# Timbre.net
KiCad netlist of a schematic drawn in EAGLE
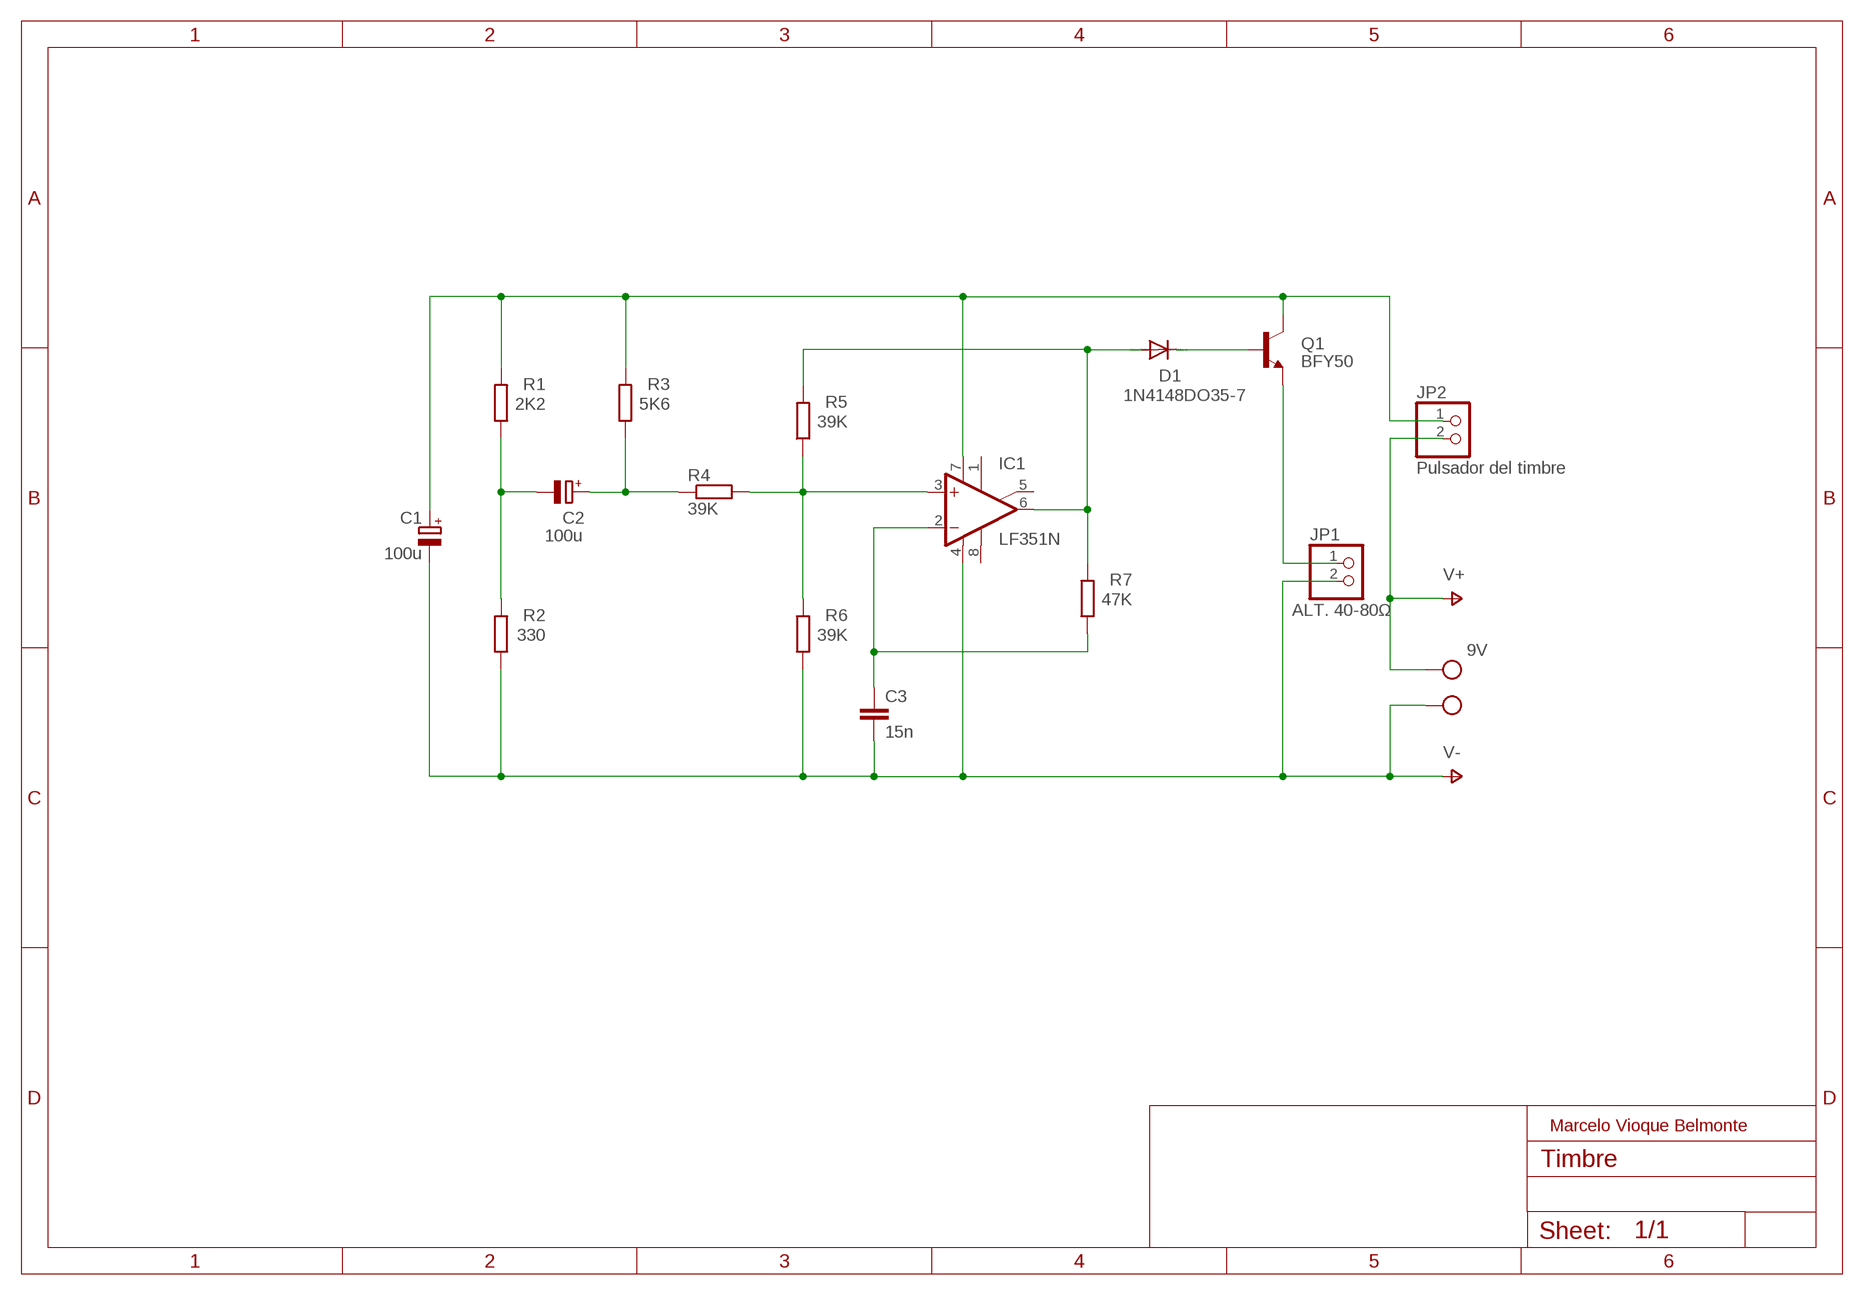
[diagram p0: schematic, sheet 1]

(export (version "E")
  (design (tool "Eeschema 10.0.6"))
  (components
    (comp (ref "C1")
      (value "100u")
      (footprint "eagle-import:E2,5-6")
      (libsource (lib "eagle-import") (part "CPOL-EUE2.5-6"))
    )
    (comp (ref "C2")
      (value "100u")
      (footprint "eagle-import:E2,5-6")
      (libsource (lib "eagle-import") (part "CPOL-EUE2.5-6"))
    )
    (comp (ref "C3")
      (value "15n")
      (footprint "eagle-import:C025_050-025X075")
      (libsource (lib "eagle-import") (part "C-EU025_050-025X075"))
    )
    (comp (ref "D1")
      (value "1N4148DO35-7")
      (footprint "eagle-import:DO35-7")
      (libsource (lib "eagle-import") (part "1N4148DO35-7"))
    )
    (comp (ref "IC1")
      (value "LF351N")
      (footprint "eagle-import:DIL08")
      (libsource (lib "eagle-import") (part "LF351N"))
    )
    (comp (ref "JP1")
      (value "ALT. 40-80Ω")
      (footprint "eagle-import:1X02")
      (libsource (lib "eagle-import") (part "PINHD-1X2"))
    )
    (comp (ref "JP2")
      (value "Pulsador del timbre")
      (footprint "eagle-import:1X02")
      (libsource (lib "eagle-import") (part "PINHD-1X2"))
    )
    (comp (ref "Q1")
      (value "BFY50")
      (footprint "eagle-import:TO39")
      (libsource (lib "eagle-import") (part "BFY50"))
    )
    (comp (ref "R1")
      (value "2K2")
      (footprint "eagle-import:0207_10")
      (libsource (lib "eagle-import") (part "R-EU_0207/10"))
    )
    (comp (ref "R2")
      (value "330")
      (footprint "eagle-import:0207_10")
      (libsource (lib "eagle-import") (part "R-EU_0207/10"))
    )
    (comp (ref "R3")
      (value "5K6")
      (footprint "eagle-import:0207_10")
      (libsource (lib "eagle-import") (part "R-EU_0207/10"))
    )
    (comp (ref "R4")
      (value "39K")
      (footprint "eagle-import:0207_10")
      (libsource (lib "eagle-import") (part "R-EU_0207/10"))
    )
    (comp (ref "R5")
      (value "39K")
      (footprint "eagle-import:0207_10")
      (libsource (lib "eagle-import") (part "R-EU_0207/10"))
    )
    (comp (ref "R6")
      (value "39K")
      (footprint "eagle-import:0207_10")
      (libsource (lib "eagle-import") (part "R-EU_0207/10"))
    )
    (comp (ref "R7")
      (value "47K")
      (footprint "eagle-import:0207_10")
      (libsource (lib "eagle-import") (part "R-EU_0207/10"))
    )
    (comp (ref "X1")
      (value "9V")
      (footprint "eagle-import:AK500_2")
      (libsource (lib "eagle-import") (part "AK500/2"))
    )
  )
  (nets
    (net (code "1") (name "Net-(C2-Pad+)") (class "Default")
      (node (ref "C2") (pin "+") (pinfunction "+_+") (pintype "passive"))
      (node (ref "R3") (pin "1") (pinfunction "1_1") (pintype "passive"))
      (node (ref "R4") (pin "1") (pinfunction "1_1") (pintype "passive"))
    )
    (net (code "2") (name "Net-(C2-Pad-)") (class "Default")
      (node (ref "C2") (pin "-") (pinfunction "-_-") (pintype "passive"))
      (node (ref "R1") (pin "1") (pinfunction "1_1") (pintype "passive"))
      (node (ref "R2") (pin "2") (pinfunction "2_2") (pintype "passive"))
    )
    (net (code "3") (name "Net-(IC1-+IN)") (class "Default")
      (node (ref "IC1") (pin "3") (pinfunction "+IN_3") (pintype "input"))
      (node (ref "R4") (pin "2") (pinfunction "2_2") (pintype "passive"))
      (node (ref "R5") (pin "1") (pinfunction "1_1") (pintype "passive"))
      (node (ref "R6") (pin "2") (pinfunction "2_2") (pintype "passive"))
    )
    (net (code "4") (name "Net-(IC1--IN)") (class "Default")
      (node (ref "C3") (pin "1") (pinfunction "1_1") (pintype "passive"))
      (node (ref "IC1") (pin "2") (pinfunction "-IN_2") (pintype "input"))
      (node (ref "R7") (pin "1") (pinfunction "1_1") (pintype "passive"))
    )
    (net (code "5") (name "Net-(IC1-OUT)") (class "Default")
      (node (ref "D1") (pin "A") (pinfunction "A_A") (pintype "passive"))
      (node (ref "IC1") (pin "6") (pinfunction "OUT_6") (pintype "output"))
      (node (ref "R5") (pin "2") (pinfunction "2_2") (pintype "passive"))
      (node (ref "R7") (pin "2") (pinfunction "2_2") (pintype "passive"))
    )
    (net (code "6") (name "Net-(IC1-V+)") (class "Default")
      (node (ref "C1") (pin "+") (pinfunction "+_+") (pintype "passive"))
      (node (ref "IC1") (pin "7") (pinfunction "V+_7") (pintype "power_in"))
      (node (ref "JP2") (pin "1") (pinfunction "1_1") (pintype "passive"))
      (node (ref "Q1") (pin "3") (pinfunction "C_3") (pintype "passive"))
      (node (ref "R1") (pin "2") (pinfunction "2_2") (pintype "passive"))
      (node (ref "R3") (pin "2") (pinfunction "2_2") (pintype "passive"))
    )
    (net (code "7") (name "Net-(Q1-B)") (class "Default")
      (node (ref "D1") (pin "C") (pinfunction "C_C") (pintype "passive"))
      (node (ref "Q1") (pin "2") (pinfunction "B_2") (pintype "passive"))
    )
    (net (code "8") (name "Net-(Q1-E)") (class "Default")
      (node (ref "JP1") (pin "1") (pinfunction "1_1") (pintype "passive"))
      (node (ref "Q1") (pin "1") (pinfunction "E_1") (pintype "passive"))
    )
    (net (code "9") (name "V+") (class "Default")
      (node (ref "JP2") (pin "2") (pinfunction "2_2") (pintype "passive"))
      (node (ref "X1") (pin "2") (pinfunction "KL_2") (pintype "passive"))
    )
    (net (code "10") (name "V-") (class "Default")
      (node (ref "C1") (pin "-") (pinfunction "-_-") (pintype "passive"))
      (node (ref "C3") (pin "2") (pinfunction "2_2") (pintype "passive"))
      (node (ref "IC1") (pin "4") (pinfunction "V-_4") (pintype "power_in"))
      (node (ref "JP1") (pin "2") (pinfunction "2_2") (pintype "passive"))
      (node (ref "R2") (pin "1") (pinfunction "1_1") (pintype "passive"))
      (node (ref "R6") (pin "1") (pinfunction "1_1") (pintype "passive"))
      (node (ref "X1") (pin "1") (pinfunction "KL_1") (pintype "passive"))
    )
    (net (code "11") (name "unconnected-(IC1-ON1-Pad1)") (class "Default")
      (node (ref "IC1") (pin "1") (pinfunction "ON1_1") (pintype "passive"))
    )
    (net (code "12") (name "unconnected-(IC1-ON2-Pad5)") (class "Default")
      (node (ref "IC1") (pin "5") (pinfunction "ON2_5") (pintype "passive"))
    )
    (net (code "13") (name "unconnected-(IC1-OPT-Pad8)") (class "Default")
      (node (ref "IC1") (pin "8") (pinfunction "OPT_8") (pintype "passive"))
    )
  )
)
